# TOP.net
KiCad netlist of a schematic drawn in Altium Designer
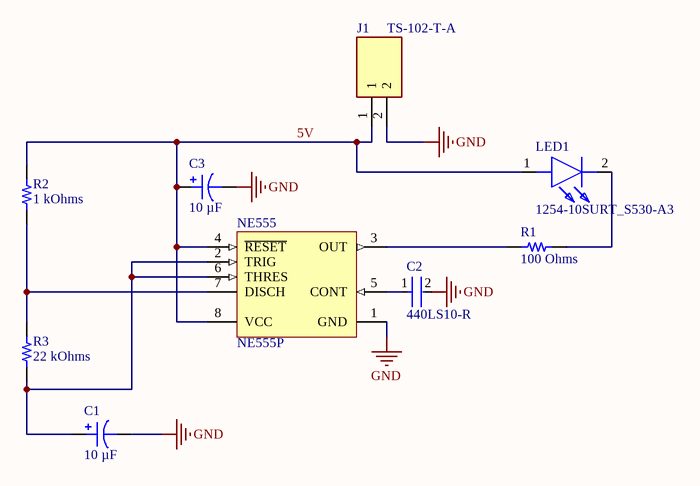
[diagram p0: TOP.SchDoc]

(export (version "E")
  (design (tool "Eeschema 10.0.6"))
  (components
    (comp (ref "C1")
      (value "10 µF")
      (footprint "CAP AL TH D8 L3.5 H12.5")
      (description "CAP ALUM 10UF 20% 100V RADIAL")
      (fields (field (name "PART NUMBER") "UKL2A100MPD1TD") (field (name "MANUFACTURER") "Nichicon"))
      (libsource (lib "Celestial") (part "Polarised Capacitor"))
    )
    (comp (ref "C2")
      (value "440LS10-R")
      (footprint "FP-440LS10-R-MFG")
      (description "CAP CER 10000PF 760VAC Y5U RDL")
      (fields (field (name "VOLTAGE") "760V") (field (name "TOLERANCE") "20%"))
      (libsource (lib "Altium Content Vault") (part "c63df4e470592b70a04075c8ad5014d"))
    )
    (comp (ref "C3")
      (value "10 µF")
      (footprint "CAP AL TH D8 L3.5 H12.5")
      (description "CAP ALUM 10UF 20% 100V RADIAL")
      (fields (field (name "PART NUMBER") "UKL2A100MPD1TD") (field (name "MANUFACTURER") "Nichicon"))
      (libsource (lib "Celestial") (part "Polarised Capacitor"))
    )
    (comp (ref "J1")
      (value "TS-102-T-A")
      (footprint "SamacSys:SAMTEC_TS-102-T-A")
      (description "Connector")
      (fields (field (name "MOUSER PART NUMBER") "200-TS102TA"))
      (libsource (lib "*") (part "TS-102-T-A"))
    )
    (comp (ref "LED1")
      (value "1254-10SURT_S530-A3")
      (footprint "SamacSys:125410SURTS530A3")
      (description "LED")
      (fields (field (name "MANUFACTURER_PART_NUMBER") "1254-10SURT/S530-A3"))
      (libsource (lib "*") (part "1254-10SURT_S530-A3"))
    )
    (comp (ref "NE555")
      (value "NE555P")
      (footprint "P0008A")
      (description "Precision Timer, 4.5 to 16 V, 0 to 70 degC, 8-Pin DIP, Pb-Free, Tube")
      (fields (field (name "MANUFACTURER") "TexasInstruments"))
      (libsource (lib "Altium Content Vault") (part "TI-NE555-P8"))
    )
    (comp (ref "R1")
      (value "100 Ohms")
      (footprint "RES 2512_6432")
      (description "RES SMD 100 OHM 5% 1W 2512")
      (fields (field (name "PART NUMBER") "CR2512-JW-101ELF") (field (name "MANUFACTURER") "Bourns Inc."))
      (libsource (lib "Celestial") (part "Resistor"))
    )
    (comp (ref "R2")
      (value "1 kOhms")
      (footprint "RES 2512_6432")
      (description "RES 1K OHM 1% 1W 2512")
      (fields
        (field (name "PART NUMBER") "RMCF2512FT1K00")
        (field (name "MANUFACTURER") "Stackpole Electronics Inc")
      )
      (libsource (lib "Celestial") (part "Resistor"))
    )
    (comp (ref "R3")
      (value "22 kOhms")
      (footprint "RES 2512_6432")
      (description "RES SMD 22K OHM 5% 3W 2512")
      (fields
        (field (name "PART NUMBER") "352222KJT")
        (field (name "MANUFACTURER") "TE Connectivity Passive Product")
      )
      (libsource (lib "Celestial") (part "Resistor"))
    )
  )
  (nets
    (net (code "1") (name "/5V") (class "Default")
      (node (ref "C3") (pin "1") (pinfunction "1_1") (pintype "passive"))
      (node (ref "J1") (pin "1") (pinfunction "1_1") (pintype "passive"))
      (node (ref "LED1") (pin "1") (pinfunction "A_1") (pintype "passive"))
      (node (ref "NE555") (pin "4") (pinfunction "~{RESET}_4") (pintype "input"))
      (node (ref "NE555") (pin "8") (pinfunction "VCC_8") (pintype "power_in"))
      (node (ref "R2") (pin "2") (pinfunction "2_2") (pintype "passive"))
    )
    (net (code "2") (name "GND") (class "Default")
      (node (ref "C1") (pin "2") (pinfunction "2_2") (pintype "passive"))
      (node (ref "C2") (pin "2") (pinfunction "2_2") (pintype "passive"))
      (node (ref "C3") (pin "2") (pinfunction "2_2") (pintype "passive"))
      (node (ref "J1") (pin "2") (pinfunction "2_2") (pintype "passive"))
      (node (ref "NE555") (pin "1") (pinfunction "GND_1") (pintype "power_in"))
    )
    (net (code "3") (name "Net-(LED1-K)") (class "Default")
      (node (ref "LED1") (pin "2") (pinfunction "K_2") (pintype "passive"))
      (node (ref "R1") (pin "2") (pinfunction "2_2") (pintype "passive"))
    )
    (net (code "4") (name "Net-(NE555-CONT)") (class "Default")
      (node (ref "C2") (pin "1") (pinfunction "1_1") (pintype "passive"))
      (node (ref "NE555") (pin "5") (pinfunction "CONT_5") (pintype "input"))
    )
    (net (code "5") (name "Net-(NE555-DISCH)") (class "Default")
      (node (ref "NE555") (pin "7") (pinfunction "DISCH_7") (pintype "open_collector"))
      (node (ref "R2") (pin "1") (pinfunction "1_1") (pintype "passive"))
      (node (ref "R3") (pin "2") (pinfunction "2_2") (pintype "passive"))
    )
    (net (code "6") (name "Net-(NE555-OUT)") (class "Default")
      (node (ref "NE555") (pin "3") (pinfunction "OUT_3") (pintype "output"))
      (node (ref "R1") (pin "1") (pinfunction "1_1") (pintype "passive"))
    )
    (net (code "7") (name "Net-(NE555-THRES)") (class "Default")
      (node (ref "C1") (pin "1") (pinfunction "1_1") (pintype "passive"))
      (node (ref "NE555") (pin "2") (pinfunction "TRIG_2") (pintype "input"))
      (node (ref "NE555") (pin "6") (pinfunction "THRES_6") (pintype "input"))
      (node (ref "R3") (pin "1") (pinfunction "1_1") (pintype "passive"))
    )
  )
)
